# teensyMotors.net
KiCad netlist of a schematic drawn in EAGLE
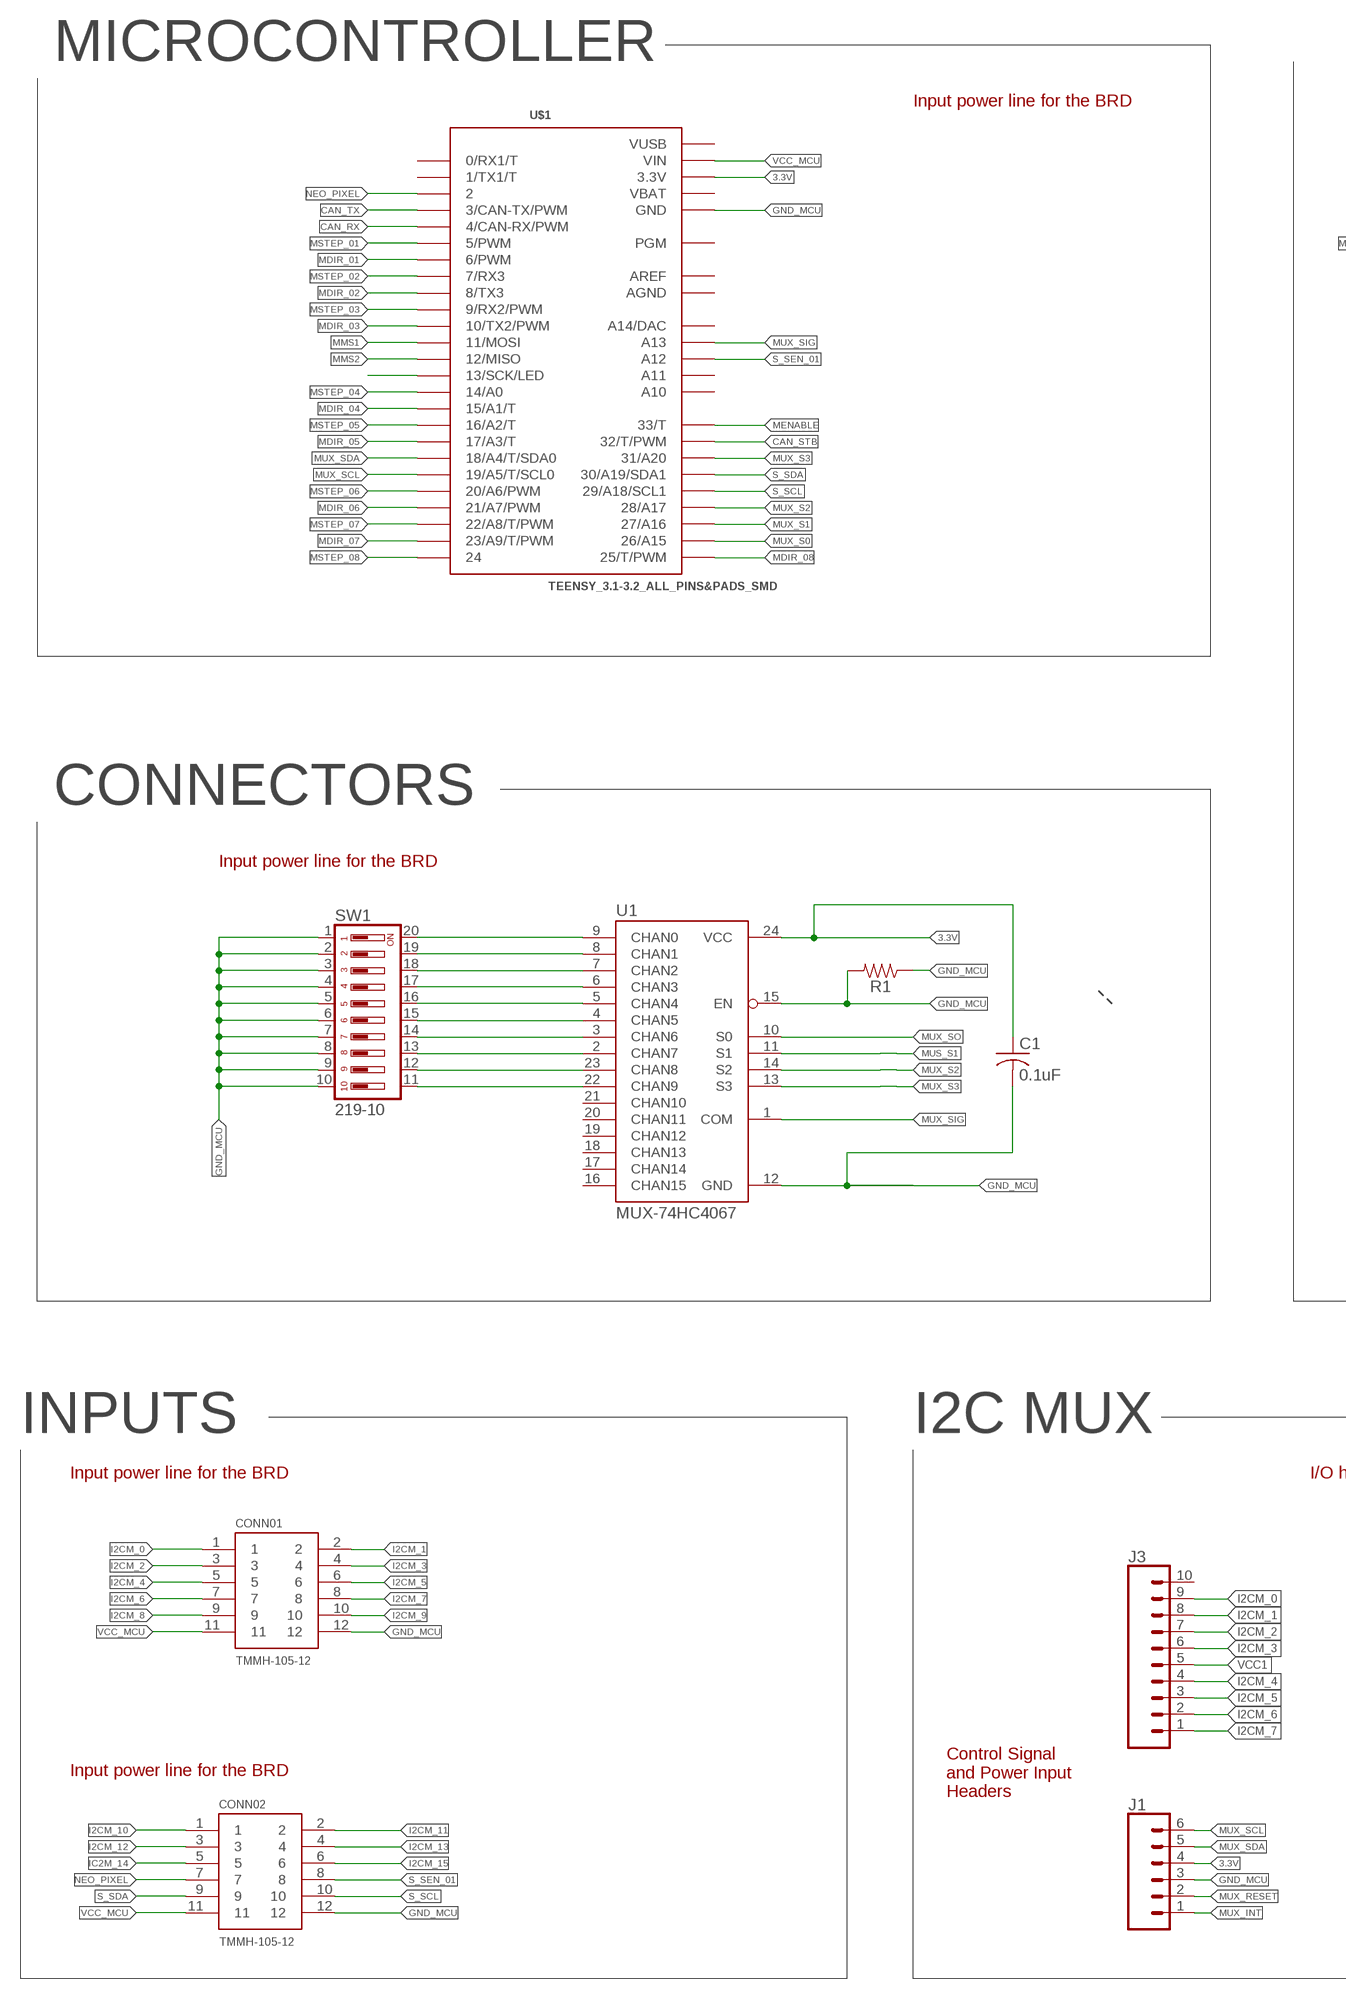
[diagram p0: schematic, sheet 1, part 1 of 2]
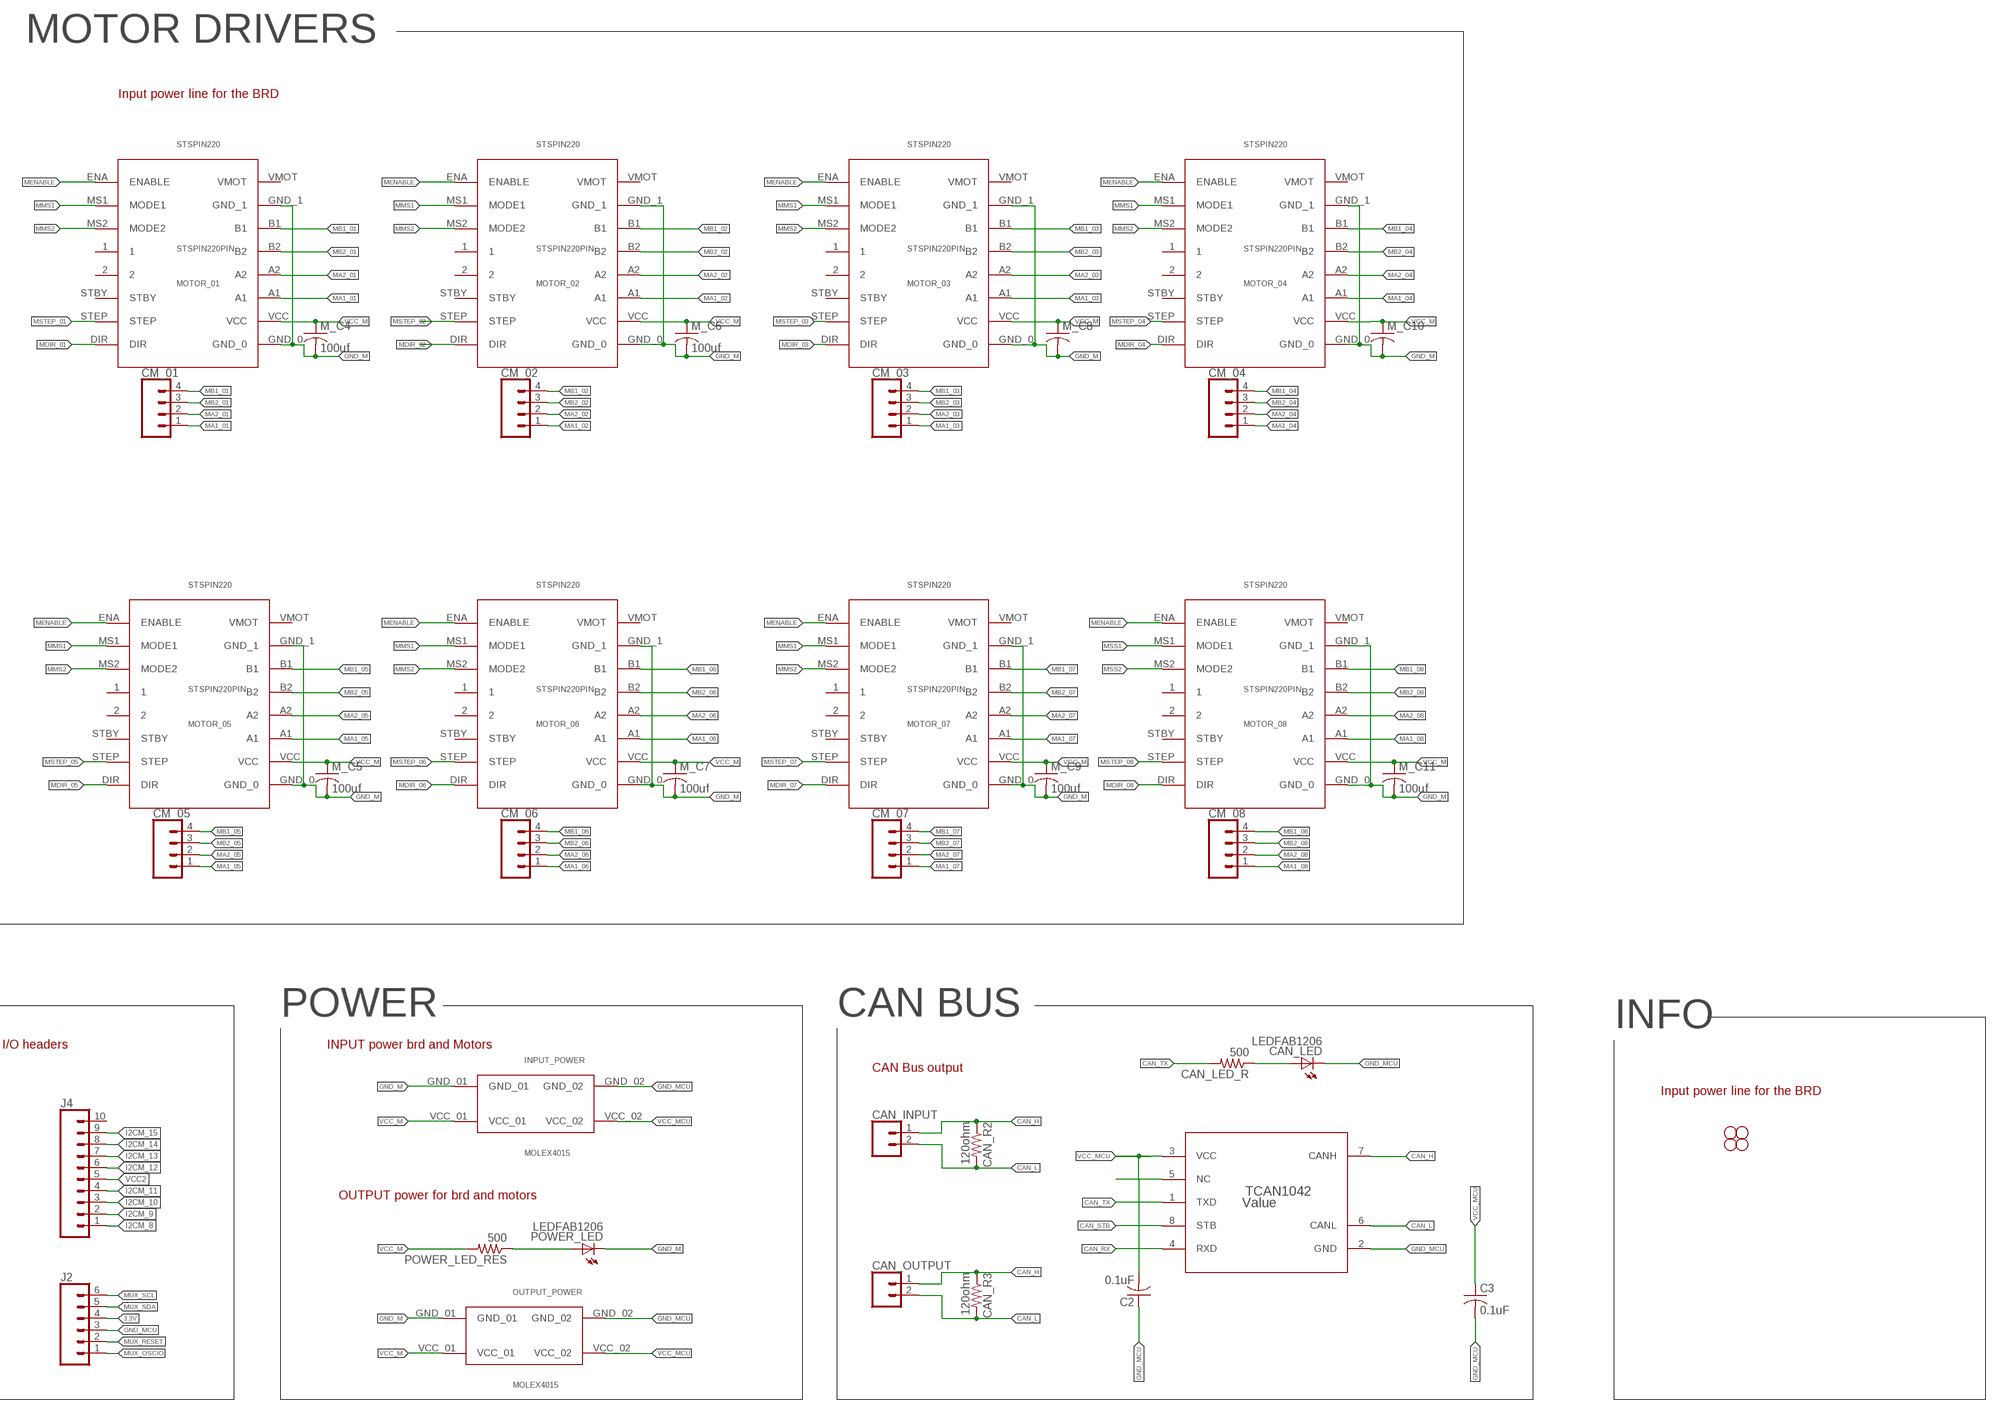
[diagram p1: schematic, sheet 1, part 2 of 2]

(export (version "E")
  (design (tool "Eeschema 10.0.6"))
  (components
    (comp (ref "C1")
      (value "0.1uF")
      (footprint "eagle-import:C1206")
      (libsource (lib "eagle-import") (part "C-USC1206"))
    )
    (comp (ref "C2")
      (value "0.1uF")
      (footprint "eagle-import:C1206")
      (libsource (lib "eagle-import") (part "C-USC1206"))
    )
    (comp (ref "C3")
      (value "0.1uF")
      (footprint "eagle-import:C1206")
      (libsource (lib "eagle-import") (part "C-USC1206"))
    )
    (comp (ref "CAN_INPUT")
      (value "CONN_02-JST-2MM-SMT")
      (footprint "eagle-import:JST-2-SMD")
      (libsource (lib "eagle-import") (part "CONN_02-JST-2MM-SMT"))
    )
    (comp (ref "CAN_LED")
      (value "LEDFAB1206")
      (footprint "eagle-import:LED1206FAB")
      (libsource (lib "eagle-import") (part "LEDFAB1206"))
    )
    (comp (ref "CAN_LED_R")
      (value "500")
      (footprint "eagle-import:R1206FAB")
      (libsource (lib "eagle-import") (part "RES-US1206FAB"))
    )
    (comp (ref "CAN_OUTPUT")
      (value "CONN_02-JST-2MM-SMT")
      (footprint "eagle-import:JST-2-SMD")
      (libsource (lib "eagle-import") (part "CONN_02-JST-2MM-SMT"))
    )
    (comp (ref "CAN_R2")
      (value "120ohm")
      (footprint "eagle-import:1206")
      (libsource (lib "eagle-import") (part "RESISTOR1206"))
    )
    (comp (ref "CAN_R3")
      (value "120ohm")
      (footprint "eagle-import:1206")
      (libsource (lib "eagle-import") (part "RESISTOR1206"))
    )
    (comp (ref "CM_01")
      (value "CONN_04SMD2")
      (footprint "eagle-import:1X04_1MM_RA")
      (libsource (lib "eagle-import") (part "CONN_04SMD2"))
    )
    (comp (ref "CM_02")
      (value "CONN_04SMD2")
      (footprint "eagle-import:1X04_1MM_RA")
      (libsource (lib "eagle-import") (part "CONN_04SMD2"))
    )
    (comp (ref "CM_03")
      (value "CONN_04SMD2")
      (footprint "eagle-import:1X04_1MM_RA")
      (libsource (lib "eagle-import") (part "CONN_04SMD2"))
    )
    (comp (ref "CM_04")
      (value "CONN_04SMD2")
      (footprint "eagle-import:1X04_1MM_RA")
      (libsource (lib "eagle-import") (part "CONN_04SMD2"))
    )
    (comp (ref "CM_05")
      (value "CONN_04SMD2")
      (footprint "eagle-import:1X04_1MM_RA")
      (libsource (lib "eagle-import") (part "CONN_04SMD2"))
    )
    (comp (ref "CM_06")
      (value "CONN_04SMD2")
      (footprint "eagle-import:1X04_1MM_RA")
      (libsource (lib "eagle-import") (part "CONN_04SMD2"))
    )
    (comp (ref "CM_07")
      (value "CONN_04SMD2")
      (footprint "eagle-import:1X04_1MM_RA")
      (libsource (lib "eagle-import") (part "CONN_04SMD2"))
    )
    (comp (ref "CM_08")
      (value "CONN_04SMD2")
      (footprint "eagle-import:1X04_1MM_RA")
      (libsource (lib "eagle-import") (part "CONN_04SMD2"))
    )
    (comp (ref "CONN01")
      (value "TMMH-105-12")
      (footprint "eagle-import:TMMH-105-12")
      (libsource (lib "eagle-import") (part "TMMH-105-12"))
    )
    (comp (ref "CONN02")
      (value "TMMH-105-12")
      (footprint "eagle-import:TMMH-105-12")
      (libsource (lib "eagle-import") (part "TMMH-105-12"))
    )
    (comp (ref "INPUT_POWER")
      (value "MOLEX4015")
      (footprint "eagle-import:MOLEX4015")
      (libsource (lib "eagle-import") (part "MOLEX4015"))
    )
    (comp (ref "J1")
      (value "CONN_06SMD_MALE")
      (footprint "eagle-import:1X06_SMD_MALE")
      (libsource (lib "eagle-import") (part "CONN_06SMD_MALE"))
    )
    (comp (ref "J2")
      (value "CONN_06SMD_MALE")
      (footprint "eagle-import:1X06_SMD_MALE")
      (libsource (lib "eagle-import") (part "CONN_06SMD_MALE"))
    )
    (comp (ref "J3")
      (value "CONN_10SMD_MALE")
      (footprint "eagle-import:1X10_SMD_MALE")
      (libsource (lib "eagle-import") (part "CONN_10SMD_MALE"))
    )
    (comp (ref "J4")
      (value "CONN_10SMD_MALE")
      (footprint "eagle-import:1X10_SMD_MALE")
      (libsource (lib "eagle-import") (part "CONN_10SMD_MALE"))
    )
    (comp (ref "MOTOR_01")
      (value "STSPIN220PIN")
      (footprint "eagle-import:STSPIN220")
      (libsource (lib "eagle-import") (part "STSPIN220PIN"))
    )
    (comp (ref "MOTOR_02")
      (value "STSPIN220PIN")
      (footprint "eagle-import:STSPIN220")
      (libsource (lib "eagle-import") (part "STSPIN220PIN"))
    )
    (comp (ref "MOTOR_03")
      (value "STSPIN220PIN")
      (footprint "eagle-import:STSPIN220")
      (libsource (lib "eagle-import") (part "STSPIN220PIN"))
    )
    (comp (ref "MOTOR_04")
      (value "STSPIN220PIN")
      (footprint "eagle-import:STSPIN220")
      (libsource (lib "eagle-import") (part "STSPIN220PIN"))
    )
    (comp (ref "MOTOR_05")
      (value "STSPIN220PIN")
      (footprint "eagle-import:STSPIN220")
      (libsource (lib "eagle-import") (part "STSPIN220PIN"))
    )
    (comp (ref "MOTOR_06")
      (value "STSPIN220PIN")
      (footprint "eagle-import:STSPIN220")
      (libsource (lib "eagle-import") (part "STSPIN220PIN"))
    )
    (comp (ref "MOTOR_07")
      (value "STSPIN220PIN")
      (footprint "eagle-import:STSPIN220")
      (libsource (lib "eagle-import") (part "STSPIN220PIN"))
    )
    (comp (ref "MOTOR_08")
      (value "STSPIN220PIN")
      (footprint "eagle-import:STSPIN220")
      (libsource (lib "eagle-import") (part "STSPIN220PIN"))
    )
    (comp (ref "M_C4")
      (value "100uf")
      (footprint "eagle-import:C1206")
      (libsource (lib "eagle-import") (part "C-USC1206"))
    )
    (comp (ref "M_C5")
      (value "100uf")
      (footprint "eagle-import:C1206")
      (libsource (lib "eagle-import") (part "C-USC1206"))
    )
    (comp (ref "M_C6")
      (value "100uf")
      (footprint "eagle-import:C1206")
      (libsource (lib "eagle-import") (part "C-USC1206"))
    )
    (comp (ref "M_C7")
      (value "100uf")
      (footprint "eagle-import:C1206")
      (libsource (lib "eagle-import") (part "C-USC1206"))
    )
    (comp (ref "M_C8")
      (value "C-USC1206")
      (footprint "eagle-import:C1206")
      (libsource (lib "eagle-import") (part "C-USC1206"))
    )
    (comp (ref "M_C9")
      (value "100uf")
      (footprint "eagle-import:C1206")
      (libsource (lib "eagle-import") (part "C-USC1206"))
    )
    (comp (ref "M_C10")
      (value "C-USC1206")
      (footprint "eagle-import:C1206")
      (libsource (lib "eagle-import") (part "C-USC1206"))
    )
    (comp (ref "M_C11")
      (value "100uf")
      (footprint "eagle-import:C1206")
      (libsource (lib "eagle-import") (part "C-USC1206"))
    )
    (comp (ref "OUTPUT_POWER")
      (value "MOLEX4015")
      (footprint "eagle-import:MOLEX4015")
      (libsource (lib "eagle-import") (part "MOLEX4015"))
    )
    (comp (ref "POWER_LED")
      (value "LEDFAB1206")
      (footprint "eagle-import:LED1206FAB")
      (libsource (lib "eagle-import") (part "LEDFAB1206"))
    )
    (comp (ref "POWER_LED_RES")
      (value "500")
      (footprint "eagle-import:R1206FAB")
      (libsource (lib "eagle-import") (part "RES-US1206FAB"))
    )
    (comp (ref "R1")
      (value "RESISTOR1206")
      (footprint "eagle-import:1206")
      (libsource (lib "eagle-import") (part "RESISTOR1206"))
    )
    (comp (ref "STANDOFF5")
      (value "STAND-OFF")
      (footprint "eagle-import:STAND-OFF")
      (libsource (lib "eagle-import") (part "STAND-OFF"))
    )
    (comp (ref "STANDOFF6")
      (value "STAND-OFF")
      (footprint "eagle-import:STAND-OFF")
      (libsource (lib "eagle-import") (part "STAND-OFF"))
    )
    (comp (ref "STANDOFF7")
      (value "STAND-OFF")
      (footprint "eagle-import:STAND-OFF")
      (libsource (lib "eagle-import") (part "STAND-OFF"))
    )
    (comp (ref "STANDOFF8")
      (value "STAND-OFF")
      (footprint "eagle-import:STAND-OFF")
      (libsource (lib "eagle-import") (part "STAND-OFF"))
    )
    (comp (ref "SW1")
      (value "219-10")
      (footprint "eagle-import:CTS-219-10")
      (fields (field (name "MF") "SLI (CML/IDI)") (field (name "MPN") "219-10PK"))
      (libsource (lib "eagle-import") (part "219-10"))
    )
    (comp (ref "TCAN1042")
      (value "Value")
      (footprint "eagle-import:D0008A_N")
      (fields (field (name "MANUFACTURER") "Texas Instruments") (field (name "PARTNUMBER") "TCAN1042DRQ1"))
      (libsource (lib "eagle-import") (part "TCAN1042DRQ1"))
    )
    (comp (ref "U$1")
      (value "TEENSY_3.1-3.2_ALL_PINS&PADS_SMD")
      (footprint "eagle-import:TEENSY_3.0-3.2_ALL_PINS_&_PADS_SMD")
      (libsource (lib "eagle-import") (part "TEENSY_3.1-3.2_ALL_PINS&PADS_SMD"))
    )
    (comp (ref "U1")
      (value "MUX-74HC4067")
      (footprint "eagle-import:SSOP24")
      (libsource (lib "eagle-import") (part "MUX-74HC4067SMD"))
    )
  )
  (nets
    (net (code "1") (name "/AGND") (class "Default")
      (node (ref "U$1") (pin "AGND") (pinfunction "AGND_AGND") (pintype "power_in"))
    )
    (net (code "2") (name "/AREF") (class "Default")
      (node (ref "U$1") (pin "AREF") (pinfunction "AREF_AREF") (pintype "power_in"))
    )
    (net (code "3") (name "/VBAT") (class "Default")
      (node (ref "U$1") (pin "VBAT") (pinfunction "VBAT_VBAT") (pintype "power_in"))
    )
    (net (code "4") (name "/VUSB") (class "Default")
      (node (ref "U$1") (pin "VUSB") (pinfunction "VUSB_VUSB") (pintype "power_in"))
    )
    (net (code "5") (name "3.3V") (class "Default")
      (node (ref "C1") (pin "1") (pinfunction "1_1") (pintype "passive"))
      (node (ref "J1") (pin "4") (pinfunction "4_4") (pintype "passive"))
      (node (ref "J2") (pin "4") (pinfunction "4_4") (pintype "passive"))
      (node (ref "U$1") (pin "3.3V") (pinfunction "3.3V_3.3V") (pintype "power_in"))
      (node (ref "U$1") (pin "3.3V1") (pinfunction "3.3V_3.3V1") (pintype "power_in"))
      (node (ref "U$1") (pin "3.3V2") (pinfunction "3.3V_3.3V2") (pintype "power_in"))
      (node (ref "U1") (pin "24") (pinfunction "VCC_24") (pintype "bidirectional"))
    )
    (net (code "6") (name "CAN_H") (class "Default")
      (node (ref "CAN_INPUT") (pin "1") (pinfunction "2_1") (pintype "passive"))
      (node (ref "CAN_OUTPUT") (pin "1") (pinfunction "2_1") (pintype "passive"))
      (node (ref "CAN_R2") (pin "1") (pinfunction "1_1") (pintype "passive"))
      (node (ref "CAN_R3") (pin "1") (pinfunction "1_1") (pintype "passive"))
      (node (ref "TCAN1042") (pin "7") (pinfunction "CANH_7") (pintype "bidirectional"))
    )
    (net (code "7") (name "CAN_L") (class "Default")
      (node (ref "CAN_INPUT") (pin "2") (pinfunction "1_2") (pintype "passive"))
      (node (ref "CAN_OUTPUT") (pin "2") (pinfunction "1_2") (pintype "passive"))
      (node (ref "CAN_R2") (pin "2") (pinfunction "2_2") (pintype "passive"))
      (node (ref "CAN_R3") (pin "2") (pinfunction "2_2") (pintype "passive"))
      (node (ref "TCAN1042") (pin "6") (pinfunction "CANL_6") (pintype "bidirectional"))
    )
    (net (code "8") (name "CAN_RX") (class "Default")
      (node (ref "TCAN1042") (pin "4") (pinfunction "RXD_4") (pintype "output"))
      (node (ref "U$1") (pin "4") (pinfunction "4/CAN-RX/PWM_4") (pintype "bidirectional"))
    )
    (net (code "9") (name "CAN_STB") (class "Default")
      (node (ref "TCAN1042") (pin "8") (pinfunction "STB_8") (pintype "input"))
      (node (ref "U$1") (pin "32") (pinfunction "32/T/PWM_32") (pintype "bidirectional"))
    )
    (net (code "10") (name "CAN_TX") (class "Default")
      (node (ref "CAN_LED_R") (pin "2") (pinfunction "2_2") (pintype "passive"))
      (node (ref "TCAN1042") (pin "1") (pinfunction "TXD_1") (pintype "input"))
      (node (ref "U$1") (pin "3") (pinfunction "3/CAN-TX/PWM_3") (pintype "bidirectional"))
    )
    (net (code "11") (name "GND_M") (class "Default")
      (node (ref "INPUT_POWER") (pin "GND_01") (pinfunction "GND_01_GND_01") (pintype "bidirectional"))
      (node (ref "MOTOR_01") (pin "GND_0") (pinfunction "GND_0_GND_0") (pintype "bidirectional"))
      (node (ref "MOTOR_01") (pin "GND_1") (pinfunction "GND_1_GND_1") (pintype "bidirectional"))
      (node (ref "MOTOR_02") (pin "GND_0") (pinfunction "GND_0_GND_0") (pintype "bidirectional"))
      (node (ref "MOTOR_02") (pin "GND_1") (pinfunction "GND_1_GND_1") (pintype "bidirectional"))
      (node (ref "MOTOR_03") (pin "GND_0") (pinfunction "GND_0_GND_0") (pintype "bidirectional"))
      (node (ref "MOTOR_03") (pin "GND_1") (pinfunction "GND_1_GND_1") (pintype "bidirectional"))
      (node (ref "MOTOR_04") (pin "GND_0") (pinfunction "GND_0_GND_0") (pintype "bidirectional"))
      (node (ref "MOTOR_04") (pin "GND_1") (pinfunction "GND_1_GND_1") (pintype "bidirectional"))
      (node (ref "MOTOR_05") (pin "GND_0") (pinfunction "GND_0_GND_0") (pintype "bidirectional"))
      (node (ref "MOTOR_05") (pin "GND_1") (pinfunction "GND_1_GND_1") (pintype "bidirectional"))
      (node (ref "MOTOR_06") (pin "GND_0") (pinfunction "GND_0_GND_0") (pintype "bidirectional"))
      (node (ref "MOTOR_06") (pin "GND_1") (pinfunction "GND_1_GND_1") (pintype "bidirectional"))
      (node (ref "MOTOR_07") (pin "GND_0") (pinfunction "GND_0_GND_0") (pintype "bidirectional"))
      (node (ref "MOTOR_07") (pin "GND_1") (pinfunction "GND_1_GND_1") (pintype "bidirectional"))
      (node (ref "MOTOR_08") (pin "GND_0") (pinfunction "GND_0_GND_0") (pintype "bidirectional"))
      (node (ref "MOTOR_08") (pin "GND_1") (pinfunction "GND_1_GND_1") (pintype "bidirectional"))
      (node (ref "M_C10") (pin "2") (pinfunction "2_2") (pintype "passive"))
      (node (ref "M_C11") (pin "2") (pinfunction "2_2") (pintype "passive"))
      (node (ref "M_C4") (pin "2") (pinfunction "2_2") (pintype "passive"))
      (node (ref "M_C5") (pin "2") (pinfunction "2_2") (pintype "passive"))
      (node (ref "M_C6") (pin "2") (pinfunction "2_2") (pintype "passive"))
      (node (ref "M_C7") (pin "2") (pinfunction "2_2") (pintype "passive"))
      (node (ref "M_C8") (pin "2") (pinfunction "2_2") (pintype "passive"))
      (node (ref "M_C9") (pin "2") (pinfunction "2_2") (pintype "passive"))
      (node (ref "OUTPUT_POWER") (pin "GND_01") (pinfunction "GND_01_GND_01") (pintype "bidirectional"))
      (node (ref "POWER_LED") (pin "2") (pinfunction "C_2") (pintype "passive"))
    )
    (net (code "12") (name "GND_MCU") (class "Default")
      (node (ref "C1") (pin "2") (pinfunction "2_2") (pintype "passive"))
      (node (ref "C2") (pin "1") (pinfunction "1_1") (pintype "passive"))
      (node (ref "C3") (pin "2") (pinfunction "2_2") (pintype "passive"))
      (node (ref "CAN_LED") (pin "2") (pinfunction "C_2") (pintype "passive"))
      (node (ref "CONN01") (pin "12") (pinfunction "12_12") (pintype "bidirectional"))
      (node (ref "CONN02") (pin "12") (pinfunction "12_12") (pintype "bidirectional"))
      (node (ref "INPUT_POWER") (pin "GND_02") (pinfunction "GND_02_GND_02") (pintype "bidirectional"))
      (node (ref "J1") (pin "3") (pinfunction "3_3") (pintype "passive"))
      (node (ref "J2") (pin "3") (pinfunction "3_3") (pintype "passive"))
      (node (ref "OUTPUT_POWER") (pin "GND_02") (pinfunction "GND_02_GND_02") (pintype "bidirectional"))
      (node (ref "R1") (pin "1") (pinfunction "1_1") (pintype "passive"))
      (node (ref "R1") (pin "2") (pinfunction "2_2") (pintype "passive"))
      (node (ref "SW1") (pin "1") (pinfunction "1_1") (pintype "passive"))
      (node (ref "SW1") (pin "10") (pinfunction "10_10") (pintype "passive"))
      (node (ref "SW1") (pin "2") (pinfunction "2_2") (pintype "passive"))
      (node (ref "SW1") (pin "3") (pinfunction "3_3") (pintype "passive"))
      (node (ref "SW1") (pin "4") (pinfunction "4_4") (pintype "passive"))
      (node (ref "SW1") (pin "5") (pinfunction "5_5") (pintype "passive"))
      (node (ref "SW1") (pin "6") (pinfunction "6_6") (pintype "passive"))
      (node (ref "SW1") (pin "7") (pinfunction "7_7") (pintype "passive"))
      (node (ref "SW1") (pin "8") (pinfunction "8_8") (pintype "passive"))
      (node (ref "SW1") (pin "9") (pinfunction "9_9") (pintype "passive"))
      (node (ref "TCAN1042") (pin "2") (pinfunction "GND_2") (pintype "power_in"))
      (node (ref "U$1") (pin "GND") (pinfunction "GND_GND") (pintype "power_in"))
      (node (ref "U$1") (pin "GND1") (pinfunction "GND_GND1") (pintype "power_in"))
      (node (ref "U$1") (pin "GND2") (pinfunction "GND_GND2") (pintype "power_in"))
      (node (ref "U1") (pin "12") (pinfunction "GND_12") (pintype "bidirectional"))
      (node (ref "U1") (pin "15") (pinfunction "EN_15") (pintype "input"))
    )
    (net (code "13") (name "I2CM_0") (class "Default")
      (node (ref "CONN01") (pin "1") (pinfunction "1_1") (pintype "bidirectional"))
      (node (ref "J3") (pin "9") (pinfunction "9_9") (pintype "passive"))
    )
    (net (code "14") (name "I2CM_1") (class "Default")
      (node (ref "CONN01") (pin "2") (pinfunction "2_2") (pintype "bidirectional"))
      (node (ref "J3") (pin "8") (pinfunction "8_8") (pintype "passive"))
    )
    (net (code "15") (name "I2CM_2") (class "Default")
      (node (ref "CONN01") (pin "3") (pinfunction "3_3") (pintype "bidirectional"))
      (node (ref "J3") (pin "7") (pinfunction "7_7") (pintype "passive"))
    )
    (net (code "16") (name "I2CM_3") (class "Default")
      (node (ref "CONN01") (pin "4") (pinfunction "4_4") (pintype "bidirectional"))
      (node (ref "J3") (pin "6") (pinfunction "6_6") (pintype "passive"))
    )
    (net (code "17") (name "I2CM_4") (class "Default")
      (node (ref "CONN01") (pin "5") (pinfunction "5_5") (pintype "bidirectional"))
      (node (ref "J3") (pin "4") (pinfunction "4_4") (pintype "passive"))
    )
    (net (code "18") (name "I2CM_5") (class "Default")
      (node (ref "CONN01") (pin "6") (pinfunction "6_6") (pintype "bidirectional"))
      (node (ref "J3") (pin "3") (pinfunction "3_3") (pintype "passive"))
    )
    (net (code "19") (name "I2CM_6") (class "Default")
      (node (ref "CONN01") (pin "7") (pinfunction "7_7") (pintype "bidirectional"))
      (node (ref "J3") (pin "2") (pinfunction "2_2") (pintype "passive"))
    )
    (net (code "20") (name "I2CM_7") (class "Default")
      (node (ref "CONN01") (pin "8") (pinfunction "8_8") (pintype "bidirectional"))
      (node (ref "J3") (pin "1") (pinfunction "1_1") (pintype "passive"))
    )
    (net (code "21") (name "I2CM_8") (class "Default")
      (node (ref "CONN01") (pin "9") (pinfunction "9_9") (pintype "bidirectional"))
      (node (ref "J4") (pin "1") (pinfunction "1_1") (pintype "passive"))
    )
    (net (code "22") (name "I2CM_9") (class "Default")
      (node (ref "CONN01") (pin "10") (pinfunction "10_10") (pintype "bidirectional"))
      (node (ref "J4") (pin "2") (pinfunction "2_2") (pintype "passive"))
    )
    (net (code "23") (name "I2CM_10") (class "Default")
      (node (ref "CONN02") (pin "1") (pinfunction "1_1") (pintype "bidirectional"))
      (node (ref "J4") (pin "3") (pinfunction "3_3") (pintype "passive"))
    )
    (net (code "24") (name "I2CM_11") (class "Default")
      (node (ref "CONN02") (pin "2") (pinfunction "2_2") (pintype "bidirectional"))
      (node (ref "J4") (pin "4") (pinfunction "4_4") (pintype "passive"))
    )
    (net (code "25") (name "I2CM_12") (class "Default")
      (node (ref "CONN02") (pin "3") (pinfunction "3_3") (pintype "bidirectional"))
      (node (ref "J4") (pin "6") (pinfunction "6_6") (pintype "passive"))
    )
    (net (code "26") (name "I2CM_13") (class "Default")
      (node (ref "CONN02") (pin "4") (pinfunction "4_4") (pintype "bidirectional"))
      (node (ref "J4") (pin "7") (pinfunction "7_7") (pintype "passive"))
    )
    (net (code "27") (name "I2CM_14") (class "Default")
      (node (ref "J4") (pin "8") (pinfunction "8_8") (pintype "passive"))
    )
    (net (code "28") (name "I2CM_15") (class "Default")
      (node (ref "CONN02") (pin "6") (pinfunction "6_6") (pintype "bidirectional"))
      (node (ref "J4") (pin "9") (pinfunction "9_9") (pintype "passive"))
    )
    (net (code "29") (name "IC2M_14") (class "Default")
      (node (ref "CONN02") (pin "5") (pinfunction "5_5") (pintype "bidirectional"))
    )
    (net (code "30") (name "MA1_01") (class "Default")
      (node (ref "CM_01") (pin "1") (pinfunction "1_1") (pintype "passive"))
      (node (ref "MOTOR_01") (pin "A1") (pinfunction "A1_A1") (pintype "bidirectional"))
    )
    (net (code "31") (name "MA1_02") (class "Default")
      (node (ref "CM_02") (pin "1") (pinfunction "1_1") (pintype "passive"))
      (node (ref "MOTOR_02") (pin "A1") (pinfunction "A1_A1") (pintype "bidirectional"))
    )
    (net (code "32") (name "MA1_03") (class "Default")
      (node (ref "CM_03") (pin "1") (pinfunction "1_1") (pintype "passive"))
      (node (ref "MOTOR_03") (pin "A1") (pinfunction "A1_A1") (pintype "bidirectional"))
    )
    (net (code "33") (name "MA1_04") (class "Default")
      (node (ref "CM_04") (pin "1") (pinfunction "1_1") (pintype "passive"))
      (node (ref "MOTOR_04") (pin "A1") (pinfunction "A1_A1") (pintype "bidirectional"))
    )
    (net (code "34") (name "MA1_05") (class "Default")
      (node (ref "CM_05") (pin "1") (pinfunction "1_1") (pintype "passive"))
      (node (ref "MOTOR_05") (pin "A1") (pinfunction "A1_A1") (pintype "bidirectional"))
    )
    (net (code "35") (name "MA1_06") (class "Default")
      (node (ref "CM_06") (pin "1") (pinfunction "1_1") (pintype "passive"))
      (node (ref "MOTOR_06") (pin "A1") (pinfunction "A1_A1") (pintype "bidirectional"))
    )
    (net (code "36") (name "MA1_07") (class "Default")
      (node (ref "CM_07") (pin "1") (pinfunction "1_1") (pintype "passive"))
      (node (ref "MOTOR_07") (pin "A1") (pinfunction "A1_A1") (pintype "bidirectional"))
    )
    (net (code "37") (name "MA1_08") (class "Default")
      (node (ref "CM_08") (pin "1") (pinfunction "1_1") (pintype "passive"))
      (node (ref "MOTOR_08") (pin "A1") (pinfunction "A1_A1") (pintype "bidirectional"))
    )
    (net (code "38") (name "MA2_01") (class "Default")
      (node (ref "CM_01") (pin "2") (pinfunction "2_2") (pintype "passive"))
      (node (ref "MOTOR_01") (pin "A2") (pinfunction "A2_A2") (pintype "bidirectional"))
    )
    (net (code "39") (name "MA2_02") (class "Default")
      (node (ref "CM_02") (pin "2") (pinfunction "2_2") (pintype "passive"))
      (node (ref "MOTOR_02") (pin "A2") (pinfunction "A2_A2") (pintype "bidirectional"))
    )
    (net (code "40") (name "MA2_03") (class "Default")
      (node (ref "CM_03") (pin "2") (pinfunction "2_2") (pintype "passive"))
      (node (ref "MOTOR_03") (pin "A2") (pinfunction "A2_A2") (pintype "bidirectional"))
    )
    (net (code "41") (name "MA2_04") (class "Default")
      (node (ref "CM_04") (pin "2") (pinfunction "2_2") (pintype "passive"))
      (node (ref "MOTOR_04") (pin "A2") (pinfunction "A2_A2") (pintype "bidirectional"))
    )
    (net (code "42") (name "MA2_05") (class "Default")
      (node (ref "CM_05") (pin "2") (pinfunction "2_2") (pintype "passive"))
      (node (ref "MOTOR_05") (pin "A2") (pinfunction "A2_A2") (pintype "bidirectional"))
    )
    (net (code "43") (name "MA2_06") (class "Default")
      (node (ref "CM_06") (pin "2") (pinfunction "2_2") (pintype "passive"))
      (node (ref "MOTOR_06") (pin "A2") (pinfunction "A2_A2") (pintype "bidirectional"))
    )
    (net (code "44") (name "MA2_07") (class "Default")
      (node (ref "CM_07") (pin "2") (pinfunction "2_2") (pintype "passive"))
      (node (ref "MOTOR_07") (pin "A2") (pinfunction "A2_A2") (pintype "bidirectional"))
    )
    (net (code "45") (name "MA2_08") (class "Default")
      (node (ref "CM_08") (pin "2") (pinfunction "2_2") (pintype "passive"))
      (node (ref "MOTOR_08") (pin "A2") (pinfunction "A2_A2") (pintype "bidirectional"))
    )
    (net (code "46") (name "MB1_01") (class "Default")
      (node (ref "CM_01") (pin "4") (pinfunction "4_4") (pintype "passive"))
      (node (ref "MOTOR_01") (pin "B1") (pinfunction "B1_B1") (pintype "bidirectional"))
    )
    (net (code "47") (name "MB1_02") (class "Default")
      (node (ref "CM_02") (pin "4") (pinfunction "4_4") (pintype "passive"))
      (node (ref "MOTOR_02") (pin "B1") (pinfunction "B1_B1") (pintype "bidirectional"))
    )
    (net (code "48") (name "MB1_03") (class "Default")
      (node (ref "CM_03") (pin "4") (pinfunction "4_4") (pintype "passive"))
      (node (ref "MOTOR_03") (pin "B1") (pinfunction "B1_B1") (pintype "bidirectional"))
    )
    (net (code "49") (name "MB1_04") (class "Default")
      (node (ref "CM_04") (pin "4") (pinfunction "4_4") (pintype "passive"))
      (node (ref "MOTOR_04") (pin "B1") (pinfunction "B1_B1") (pintype "bidirectional"))
    )
    (net (code "50") (name "MB1_05") (class "Default")
      (node (ref "CM_05") (pin "4") (pinfunction "4_4") (pintype "passive"))
      (node (ref "MOTOR_05") (pin "B1") (pinfunction "B1_B1") (pintype "bidirectional"))
    )
    (net (code "51") (name "MB1_06") (class "Default")
      (node (ref "CM_06") (pin "4") (pinfunction "4_4") (pintype "passive"))
      (node (ref "MOTOR_06") (pin "B1") (pinfunction "B1_B1") (pintype "bidirectional"))
    )
    (net (code "52") (name "MB1_07") (class "Default")
      (node (ref "CM_07") (pin "4") (pinfunction "4_4") (pintype "passive"))
      (node (ref "MOTOR_07") (pin "B1") (pinfunction "B1_B1") (pintype "bidirectional"))
    )
    (net (code "53") (name "MB1_08") (class "Default")
      (node (ref "CM_08") (pin "4") (pinfunction "4_4") (pintype "passive"))
      (node (ref "MOTOR_08") (pin "B1") (pinfunction "B1_B1") (pintype "bidirectional"))
    )
    (net (code "54") (name "MB2_01") (class "Default")
      (node (ref "CM_01") (pin "3") (pinfunction "3_3") (pintype "passive"))
      (node (ref "MOTOR_01") (pin "B2") (pinfunction "B2_B2") (pintype "bidirectional"))
    )
    (net (code "55") (name "MB2_02") (class "Default")
      (node (ref "CM_02") (pin "3") (pinfunction "3_3") (pintype "passive"))
      (node (ref "MOTOR_02") (pin "B2") (pinfunction "B2_B2") (pintype "bidirectional"))
    )
    (net (code "56") (name "MB2_03") (class "Default")
      (node (ref "CM_03") (pin "3") (pinfunction "3_3") (pintype "passive"))
      (node (ref "MOTOR_03") (pin "B2") (pinfunction "B2_B2") (pintype "bidirectional"))
    )
    (net (code "57") (name "MB2_04") (class "Default")
      (node (ref "CM_04") (pin "3") (pinfunction "3_3") (pintype "passive"))
      (node (ref "MOTOR_04") (pin "B2") (pinfunction "B2_B2") (pintype "bidirectional"))
    )
    (net (code "58") (name "MB2_05") (class "Default")
      (node (ref "CM_05") (pin "3") (pinfunction "3_3") (pintype "passive"))
      (node (ref "MOTOR_05") (pin "B2") (pinfunction "B2_B2") (pintype "bidirectional"))
    )
    (net (code "59") (name "MB2_06") (class "Default")
      (node (ref "CM_06") (pin "3") (pinfunction "3_3") (pintype "passive"))
      (node (ref "MOTOR_06") (pin "B2") (pinfunction "B2_B2") (pintype "bidirectional"))
    )
    (net (code "60") (name "MB2_07") (class "Default")
      (node (ref "CM_07") (pin "3") (pinfunction "3_3") (pintype "passive"))
      (node (ref "MOTOR_07") (pin "B2") (pinfunction "B2_B2") (pintype "bidirectional"))
    )
    (net (code "61") (name "MB2_08") (class "Default")
      (node (ref "CM_08") (pin "3") (pinfunction "3_3") (pintype "passive"))
      (node (ref "MOTOR_08") (pin "B2") (pinfunction "B2_B2") (pintype "bidirectional"))
    )
    (net (code "62") (name "MDIR_01") (class "Default")
      (node (ref "MOTOR_01") (pin "DIR") (pinfunction "DIR_DIR") (pintype "bidirectional"))
      (node (ref "U$1") (pin "6") (pinfunction "6/PWM_6") (pintype "bidirectional"))
    )
    (net (code "63") (name "MDIR_02") (class "Default")
      (node (ref "MOTOR_02") (pin "DIR") (pinfunction "DIR_DIR") (pintype "bidirectional"))
      (node (ref "U$1") (pin "8") (pinfunction "8/TX3_8") (pintype "bidirectional"))
    )
    (net (code "64") (name "MDIR_03") (class "Default")
      (node (ref "MOTOR_03") (pin "DIR") (pinfunction "DIR_DIR") (pintype "bidirectional"))
      (node (ref "U$1") (pin "10") (pinfunction "10/TX2/PWM_10") (pintype "bidirectional"))
    )
    (net (code "65") (name "MDIR_04") (class "Default")
      (node (ref "MOTOR_04") (pin "DIR") (pinfunction "DIR_DIR") (pintype "bidirectional"))
      (node (ref "U$1") (pin "15/A1") (pinfunction "15/A1/T_15/A1") (pintype "bidirectional"))
    )
    (net (code "66") (name "MDIR_05") (class "Default")
      (node (ref "MOTOR_05") (pin "DIR") (pinfunction "DIR_DIR") (pintype "bidirectional"))
      (node (ref "U$1") (pin "17/A3") (pinfunction "17/A3/T_17/A3") (pintype "bidirectional"))
    )
    (net (code "67") (name "MDIR_06") (class "Default")
      (node (ref "MOTOR_06") (pin "DIR") (pinfunction "DIR_DIR") (pintype "bidirectional"))
      (node (ref "U$1") (pin "21/A7") (pinfunction "21/A7/PWM_21/A7") (pintype "bidirectional"))
    )
    (net (code "68") (name "MDIR_07") (class "Default")
      (node (ref "MOTOR_07") (pin "DIR") (pinfunction "DIR_DIR") (pintype "bidirectional"))
      (node (ref "U$1") (pin "23/A9") (pinfunction "23/A9/T/PWM_23/A9") (pintype "bidirectional"))
    )
    (net (code "69") (name "MDIR_08") (class "Default")
      (node (ref "MOTOR_08") (pin "DIR") (pinfunction "DIR_DIR") (pintype "bidirectional"))
      (node (ref "U$1") (pin "25") (pinfunction "25/T/PWM_25") (pintype "bidirectional"))
    )
    (net (code "70") (name "MENABLE") (class "Default")
      (node (ref "MOTOR_01") (pin "ENA") (pinfunction "ENABLE_ENA") (pintype "bidirectional"))
      (node (ref "MOTOR_02") (pin "ENA") (pinfunction "ENABLE_ENA") (pintype "bidirectional"))
      (node (ref "MOTOR_03") (pin "ENA") (pinfunction "ENABLE_ENA") (pintype "bidirectional"))
      (node (ref "MOTOR_04") (pin "ENA") (pinfunction "ENABLE_ENA") (pintype "bidirectional"))
      (node (ref "MOTOR_05") (pin "ENA") (pinfunction "ENABLE_ENA") (pintype "bidirectional"))
      (node (ref "MOTOR_06") (pin "ENA") (pinfunction "ENABLE_ENA") (pintype "bidirectional"))
      (node (ref "MOTOR_07") (pin "ENA") (pinfunction "ENABLE_ENA") (pintype "bidirectional"))
      (node (ref "MOTOR_08") (pin "ENA") (pinfunction "ENABLE_ENA") (pintype "bidirectional"))
      (node (ref "U$1") (pin "33") (pinfunction "33/T_33") (pintype "bidirectional"))
    )
    (net (code "71") (name "MMS1") (class "Default")
      (node (ref "MOTOR_01") (pin "MS1") (pinfunction "MODE1_MS1") (pintype "bidirectional"))
      (node (ref "MOTOR_02") (pin "MS1") (pinfunction "MODE1_MS1") (pintype "bidirectional"))
      (node (ref "MOTOR_03") (pin "MS1") (pinfunction "MODE1_MS1") (pintype "bidirectional"))
      (node (ref "MOTOR_04") (pin "MS1") (pinfunction "MODE1_MS1") (pintype "bidirectional"))
      (node (ref "MOTOR_05") (pin "MS1") (pinfunction "MODE1_MS1") (pintype "bidirectional"))
      (node (ref "MOTOR_06") (pin "MS1") (pinfunction "MODE1_MS1") (pintype "bidirectional"))
      (node (ref "MOTOR_07") (pin "MS1") (pinfunction "MODE1_MS1") (pintype "bidirectional"))
      (node (ref "U$1") (pin "11") (pinfunction "11/MOSI_11") (pintype "bidirectional"))
    )
    (net (code "72") (name "MMS2") (class "Default")
      (node (ref "MOTOR_01") (pin "MS2") (pinfunction "MODE2_MS2") (pintype "bidirectional"))
      (node (ref "MOTOR_02") (pin "MS2") (pinfunction "MODE2_MS2") (pintype "bidirectional"))
      (node (ref "MOTOR_03") (pin "MS2") (pinfunction "MODE2_MS2") (pintype "bidirectional"))
      (node (ref "MOTOR_04") (pin "MS2") (pinfunction "MODE2_MS2") (pintype "bidirectional"))
      (node (ref "MOTOR_05") (pin "MS2") (pinfunction "MODE2_MS2") (pintype "bidirectional"))
      (node (ref "MOTOR_06") (pin "MS2") (pinfunction "MODE2_MS2") (pintype "bidirectional"))
      (node (ref "MOTOR_07") (pin "MS2") (pinfunction "MODE2_MS2") (pintype "bidirectional"))
      (node (ref "U$1") (pin "12") (pinfunction "12/MISO_12") (pintype "bidirectional"))
    )
    (net (code "73") (name "MSS1") (class "Default")
      (node (ref "MOTOR_08") (pin "MS1") (pinfunction "MODE1_MS1") (pintype "bidirectional"))
    )
    (net (code "74") (name "MSS2") (class "Default")
      (node (ref "MOTOR_08") (pin "MS2") (pinfunction "MODE2_MS2") (pintype "bidirectional"))
    )
    (net (code "75") (name "MSTEP_01") (class "Default")
      (node (ref "MOTOR_01") (pin "STEP") (pinfunction "STEP_STEP") (pintype "bidirectional"))
      (node (ref "U$1") (pin "5") (pinfunction "5/PWM_5") (pintype "bidirectional"))
    )
    (net (code "76") (name "MSTEP_02") (class "Default")
      (node (ref "MOTOR_02") (pin "STEP") (pinfunction "STEP_STEP") (pintype "bidirectional"))
      (node (ref "U$1") (pin "7") (pinfunction "7/RX3_7") (pintype "bidirectional"))
    )
    (net (code "77") (name "MSTEP_03") (class "Default")
      (node (ref "MOTOR_03") (pin "STEP") (pinfunction "STEP_STEP") (pintype "bidirectional"))
      (node (ref "U$1") (pin "9") (pinfunction "9/RX2/PWM_9") (pintype "bidirectional"))
    )
    (net (code "78") (name "MSTEP_04") (class "Default")
      (node (ref "MOTOR_04") (pin "STEP") (pinfunction "STEP_STEP") (pintype "bidirectional"))
      (node (ref "U$1") (pin "14/A0") (pinfunction "14/A0_14/A0") (pintype "bidirectional"))
    )
    (net (code "79") (name "MSTEP_05") (class "Default")
      (node (ref "MOTOR_05") (pin "STEP") (pinfunction "STEP_STEP") (pintype "bidirectional"))
      (node (ref "U$1") (pin "16/A2") (pinfunction "16/A2/T_16/A2") (pintype "bidirectional"))
    )
    (net (code "80") (name "MSTEP_06") (class "Default")
      (node (ref "MOTOR_06") (pin "STEP") (pinfunction "STEP_STEP") (pintype "bidirectional"))
      (node (ref "U$1") (pin "20/A6") (pinfunction "20/A6/PWM_20/A6") (pintype "bidirectional"))
    )
    (net (code "81") (name "MSTEP_07") (class "Default")
      (node (ref "MOTOR_07") (pin "STEP") (pinfunction "STEP_STEP") (pintype "bidirectional"))
      (node (ref "U$1") (pin "22/A8") (pinfunction "22/A8/T/PWM_22/A8") (pintype "bidirectional"))
    )
    (net (code "82") (name "MSTEP_08") (class "Default")
      (node (ref "MOTOR_08") (pin "STEP") (pinfunction "STEP_STEP") (pintype "bidirectional"))
      (node (ref "U$1") (pin "24") (pinfunction "24_24") (pintype "bidirectional"))
    )
    (net (code "83") (name "MUS_S1") (class "Default")
      (node (ref "U1") (pin "11") (pinfunction "S1_11") (pintype "input"))
    )
    (net (code "84") (name "MUX_INT") (class "Default")
      (node (ref "J1") (pin "1") (pinfunction "1_1") (pintype "passive"))
    )
    (net (code "85") (name "MUX_OSCIO") (class "Default")
      (node (ref "J2") (pin "1") (pinfunction "1_1") (pintype "passive"))
    )
    (net (code "86") (name "MUX_RESET") (class "Default")
      (node (ref "J1") (pin "2") (pinfunction "2_2") (pintype "passive"))
      (node (ref "J2") (pin "2") (pinfunction "2_2") (pintype "passive"))
    )
    (net (code "87") (name "MUX_S0") (class "Default")
      (node (ref "U$1") (pin "26") (pinfunction "26/A15_26") (pintype "bidirectional"))
    )
    (net (code "88") (name "MUX_S1") (class "Default")
      (node (ref "U$1") (pin "27") (pinfunction "27/A16_27") (pintype "bidirectional"))
    )
    (net (code "89") (name "MUX_S2") (class "Default")
      (node (ref "U$1") (pin "28") (pinfunction "28/A17_28") (pintype "bidirectional"))
      (node (ref "U1") (pin "14") (pinfunction "S2_14") (pintype "input"))
    )
    (net (code "90") (name "MUX_S3") (class "Default")
      (node (ref "U$1") (pin "31") (pinfunction "31/A20_31") (pintype "bidirectional"))
      (node (ref "U1") (pin "13") (pinfunction "S3_13") (pintype "input"))
    )
    (net (code "91") (name "MUX_SCL") (class "Default")
      (node (ref "J1") (pin "6") (pinfunction "6_6") (pintype "passive"))
      (node (ref "J2") (pin "6") (pinfunction "6_6") (pintype "passive"))
      (node (ref "U$1") (pin "19/A5") (pinfunction "19/A5/T/SCL0_19/A5") (pintype "bidirectional"))
    )
    (net (code "92") (name "MUX_SDA") (class "Default")
      (node (ref "J1") (pin "5") (pinfunction "5_5") (pintype "passive"))
      (node (ref "J2") (pin "5") (pinfunction "5_5") (pintype "passive"))
      (node (ref "U$1") (pin "18/A4") (pinfunction "18/A4/T/SDA0_18/A4") (pintype "bidirectional"))
    )
    (net (code "93") (name "MUX_SIG") (class "Default")
      (node (ref "U$1") (pin "A13") (pinfunction "A13_A13") (pintype "bidirectional"))
      (node (ref "U1") (pin "1") (pinfunction "COM_1") (pintype "bidirectional"))
    )
    (net (code "94") (name "MUX_SO") (class "Default")
      (node (ref "U1") (pin "10") (pinfunction "S0_10") (pintype "input"))
    )
    (net (code "95") (name "NEO_PIXEL") (class "Default")
      (node (ref "CONN02") (pin "7") (pinfunction "7_7") (pintype "bidirectional"))
      (node (ref "U$1") (pin "2") (pinfunction "2_2") (pintype "bidirectional"))
    )
    (net (code "96") (name "Net-(CAN_LED-A)") (class "Default")
      (node (ref "CAN_LED") (pin "1") (pinfunction "A_1") (pintype "passive"))
      (node (ref "CAN_LED_R") (pin "1") (pinfunction "1_1") (pintype "passive"))
    )
    (net (code "97") (name "Net-(POWER_LED-A)") (class "Default")
      (node (ref "POWER_LED") (pin "1") (pinfunction "A_1") (pintype "passive"))
      (node (ref "POWER_LED_RES") (pin "1") (pinfunction "1_1") (pintype "passive"))
    )
    (net (code "98") (name "Net-(U1-CHAN0)") (class "Default")
      (node (ref "SW1") (pin "20") (pinfunction "20_20") (pintype "passive"))
      (node (ref "U1") (pin "9") (pinfunction "CHAN0_9") (pintype "bidirectional"))
    )
    (net (code "99") (name "Net-(U1-CHAN1)") (class "Default")
      (node (ref "SW1") (pin "19") (pinfunction "19_19") (pintype "passive"))
      (node (ref "U1") (pin "8") (pinfunction "CHAN1_8") (pintype "bidirectional"))
    )
    (net (code "100") (name "Net-(U1-CHAN2)") (class "Default")
      (node (ref "SW1") (pin "18") (pinfunction "18_18") (pintype "passive"))
      (node (ref "U1") (pin "7") (pinfunction "CHAN2_7") (pintype "bidirectional"))
    )
    (net (code "101") (name "Net-(U1-CHAN3)") (class "Default")
      (node (ref "SW1") (pin "17") (pinfunction "17_17") (pintype "passive"))
      (node (ref "U1") (pin "6") (pinfunction "CHAN3_6") (pintype "bidirectional"))
    )
    (net (code "102") (name "Net-(U1-CHAN4)") (class "Default")
      (node (ref "SW1") (pin "16") (pinfunction "16_16") (pintype "passive"))
      (node (ref "U1") (pin "5") (pinfunction "CHAN4_5") (pintype "bidirectional"))
    )
    (net (code "103") (name "Net-(U1-CHAN5)") (class "Default")
      (node (ref "SW1") (pin "15") (pinfunction "15_15") (pintype "passive"))
      (node (ref "U1") (pin "4") (pinfunction "CHAN5_4") (pintype "bidirectional"))
    )
    (net (code "104") (name "Net-(U1-CHAN6)") (class "Default")
      (node (ref "SW1") (pin "14") (pinfunction "14_14") (pintype "passive"))
      (node (ref "U1") (pin "3") (pinfunction "CHAN6_3") (pintype "bidirectional"))
    )
    (net (code "105") (name "Net-(U1-CHAN7)") (class "Default")
      (node (ref "SW1") (pin "13") (pinfunction "13_13") (pintype "passive"))
      (node (ref "U1") (pin "2") (pinfunction "CHAN7_2") (pintype "bidirectional"))
    )
    (net (code "106") (name "Net-(U1-CHAN8)") (class "Default")
      (node (ref "SW1") (pin "12") (pinfunction "12_12") (pintype "passive"))
      (node (ref "U1") (pin "23") (pinfunction "CHAN8_23") (pintype "bidirectional"))
    )
    (net (code "107") (name "Net-(U1-CHAN9)") (class "Default")
      (node (ref "SW1") (pin "11") (pinfunction "11_11") (pintype "passive"))
      (node (ref "U1") (pin "22") (pinfunction "CHAN9_22") (pintype "bidirectional"))
    )
    (net (code "108") (name "S_SCL") (class "Default")
      (node (ref "CONN02") (pin "10") (pinfunction "10_10") (pintype "bidirectional"))
      (node (ref "U$1") (pin "29") (pinfunction "29/A18/SCL1_29") (pintype "bidirectional"))
    )
    (net (code "109") (name "S_SDA") (class "Default")
      (node (ref "CONN02") (pin "9") (pinfunction "9_9") (pintype "bidirectional"))
      (node (ref "U$1") (pin "30") (pinfunction "30/A19/SDA1_30") (pintype "bidirectional"))
    )
    (net (code "110") (name "S_SEN_01") (class "Default")
      (node (ref "CONN02") (pin "8") (pinfunction "8_8") (pintype "bidirectional"))
      (node (ref "U$1") (pin "A12") (pinfunction "A12_A12") (pintype "bidirectional"))
    )
    (net (code "111") (name "VCC1") (class "Default")
      (node (ref "J3") (pin "5") (pinfunction "5_5") (pintype "passive"))
    )
    (net (code "112") (name "VCC2") (class "Default")
      (node (ref "J4") (pin "5") (pinfunction "5_5") (pintype "passive"))
    )
    (net (code "113") (name "VCC_M") (class "Default")
      (node (ref "INPUT_POWER") (pin "VCC_01") (pinfunction "VCC_01_VCC_01") (pintype "bidirectional"))
      (node (ref "MOTOR_01") (pin "VCC") (pinfunction "VCC_VCC") (pintype "bidirectional"))
      (node (ref "MOTOR_02") (pin "VCC") (pinfunction "VCC_VCC") (pintype "bidirectional"))
      (node (ref "MOTOR_03") (pin "VCC") (pinfunction "VCC_VCC") (pintype "bidirectional"))
      (node (ref "MOTOR_04") (pin "VCC") (pinfunction "VCC_VCC") (pintype "bidirectional"))
      (node (ref "MOTOR_05") (pin "VCC") (pinfunction "VCC_VCC") (pintype "bidirectional"))
      (node (ref "MOTOR_06") (pin "VCC") (pinfunction "VCC_VCC") (pintype "bidirectional"))
      (node (ref "MOTOR_07") (pin "VCC") (pinfunction "VCC_VCC") (pintype "bidirectional"))
      (node (ref "MOTOR_08") (pin "VCC") (pinfunction "VCC_VCC") (pintype "bidirectional"))
      (node (ref "M_C10") (pin "1") (pinfunction "1_1") (pintype "passive"))
      (node (ref "M_C11") (pin "1") (pinfunction "1_1") (pintype "passive"))
      (node (ref "M_C4") (pin "1") (pinfunction "1_1") (pintype "passive"))
      (node (ref "M_C5") (pin "1") (pinfunction "1_1") (pintype "passive"))
      (node (ref "M_C6") (pin "1") (pinfunction "1_1") (pintype "passive"))
      (node (ref "M_C7") (pin "1") (pinfunction "1_1") (pintype "passive"))
      (node (ref "M_C8") (pin "1") (pinfunction "1_1") (pintype "passive"))
      (node (ref "M_C9") (pin "1") (pinfunction "1_1") (pintype "passive"))
      (node (ref "OUTPUT_POWER") (pin "VCC_01") (pinfunction "VCC_01_VCC_01") (pintype "bidirectional"))
      (node (ref "POWER_LED_RES") (pin "2") (pinfunction "2_2") (pintype "passive"))
    )
    (net (code "114") (name "VCC_MCU") (class "Default")
      (node (ref "C2") (pin "2") (pinfunction "2_2") (pintype "passive"))
      (node (ref "C3") (pin "1") (pinfunction "1_1") (pintype "passive"))
      (node (ref "CONN01") (pin "11") (pinfunction "11_11") (pintype "bidirectional"))
      (node (ref "CONN02") (pin "11") (pinfunction "11_11") (pintype "bidirectional"))
      (node (ref "INPUT_POWER") (pin "VCC_02") (pinfunction "VCC_02_VCC_02") (pintype "bidirectional"))
      (node (ref "OUTPUT_POWER") (pin "VCC_02") (pinfunction "VCC_02_VCC_02") (pintype "bidirectional"))
      (node (ref "TCAN1042") (pin "3") (pinfunction "VCC_3") (pintype "power_in"))
      (node (ref "U$1") (pin "VIN") (pinfunction "VIN_VIN") (pintype "power_in"))
    )
    (net (code "115") (name "unconnected-(J3-Pad10)") (class "Default")
      (node (ref "J3") (pin "10") (pinfunction "10_10") (pintype "passive"))
    )
    (net (code "116") (name "unconnected-(J4-Pad10)") (class "Default")
      (node (ref "J4") (pin "10") (pinfunction "10_10") (pintype "passive"))
    )
    (net (code "117") (name "unconnected-(MOTOR_01-Pad1)") (class "Default")
      (node (ref "MOTOR_01") (pin "1") (pinfunction "1_1") (pintype "bidirectional"))
    )
    (net (code "118") (name "unconnected-(MOTOR_01-Pad2)") (class "Default")
      (node (ref "MOTOR_01") (pin "2") (pinfunction "2_2") (pintype "bidirectional"))
    )
    (net (code "119") (name "unconnected-(MOTOR_01-PadSTBY)") (class "Default")
      (node (ref "MOTOR_01") (pin "STBY") (pinfunction "STBY_STBY") (pintype "bidirectional"))
    )
    (net (code "120") (name "unconnected-(MOTOR_01-PadVMOT)") (class "Default")
      (node (ref "MOTOR_01") (pin "VMOT") (pinfunction "VMOT_VMOT") (pintype "bidirectional"))
    )
    (net (code "121") (name "unconnected-(MOTOR_02-Pad1)") (class "Default")
      (node (ref "MOTOR_02") (pin "1") (pinfunction "1_1") (pintype "bidirectional"))
    )
    (net (code "122") (name "unconnected-(MOTOR_02-Pad2)") (class "Default")
      (node (ref "MOTOR_02") (pin "2") (pinfunction "2_2") (pintype "bidirectional"))
    )
    (net (code "123") (name "unconnected-(MOTOR_02-PadSTBY)") (class "Default")
      (node (ref "MOTOR_02") (pin "STBY") (pinfunction "STBY_STBY") (pintype "bidirectional"))
    )
    (net (code "124") (name "unconnected-(MOTOR_02-PadVMOT)") (class "Default")
      (node (ref "MOTOR_02") (pin "VMOT") (pinfunction "VMOT_VMOT") (pintype "bidirectional"))
    )
    (net (code "125") (name "unconnected-(MOTOR_03-Pad1)") (class "Default")
      (node (ref "MOTOR_03") (pin "1") (pinfunction "1_1") (pintype "bidirectional"))
    )
    (net (code "126") (name "unconnected-(MOTOR_03-Pad2)") (class "Default")
      (node (ref "MOTOR_03") (pin "2") (pinfunction "2_2") (pintype "bidirectional"))
    )
    (net (code "127") (name "unconnected-(MOTOR_03-PadSTBY)") (class "Default")
      (node (ref "MOTOR_03") (pin "STBY") (pinfunction "STBY_STBY") (pintype "bidirectional"))
    )
    (net (code "128") (name "unconnected-(MOTOR_03-PadVMOT)") (class "Default")
      (node (ref "MOTOR_03") (pin "VMOT") (pinfunction "VMOT_VMOT") (pintype "bidirectional"))
    )
    (net (code "129") (name "unconnected-(MOTOR_04-Pad1)") (class "Default")
      (node (ref "MOTOR_04") (pin "1") (pinfunction "1_1") (pintype "bidirectional"))
    )
    (net (code "130") (name "unconnected-(MOTOR_04-Pad2)") (class "Default")
      (node (ref "MOTOR_04") (pin "2") (pinfunction "2_2") (pintype "bidirectional"))
    )
    (net (code "131") (name "unconnected-(MOTOR_04-PadSTBY)") (class "Default")
      (node (ref "MOTOR_04") (pin "STBY") (pinfunction "STBY_STBY") (pintype "bidirectional"))
    )
    (net (code "132") (name "unconnected-(MOTOR_04-PadVMOT)") (class "Default")
      (node (ref "MOTOR_04") (pin "VMOT") (pinfunction "VMOT_VMOT") (pintype "bidirectional"))
    )
    (net (code "133") (name "unconnected-(MOTOR_05-Pad1)") (class "Default")
      (node (ref "MOTOR_05") (pin "1") (pinfunction "1_1") (pintype "bidirectional"))
    )
    (net (code "134") (name "unconnected-(MOTOR_05-Pad2)") (class "Default")
      (node (ref "MOTOR_05") (pin "2") (pinfunction "2_2") (pintype "bidirectional"))
    )
    (net (code "135") (name "unconnected-(MOTOR_05-PadSTBY)") (class "Default")
      (node (ref "MOTOR_05") (pin "STBY") (pinfunction "STBY_STBY") (pintype "bidirectional"))
    )
    (net (code "136") (name "unconnected-(MOTOR_05-PadVMOT)") (class "Default")
      (node (ref "MOTOR_05") (pin "VMOT") (pinfunction "VMOT_VMOT") (pintype "bidirectional"))
    )
    (net (code "137") (name "unconnected-(MOTOR_06-Pad1)") (class "Default")
      (node (ref "MOTOR_06") (pin "1") (pinfunction "1_1") (pintype "bidirectional"))
    )
    (net (code "138") (name "unconnected-(MOTOR_06-Pad2)") (class "Default")
      (node (ref "MOTOR_06") (pin "2") (pinfunction "2_2") (pintype "bidirectional"))
    )
    (net (code "139") (name "unconnected-(MOTOR_06-PadSTBY)") (class "Default")
      (node (ref "MOTOR_06") (pin "STBY") (pinfunction "STBY_STBY") (pintype "bidirectional"))
    )
    (net (code "140") (name "unconnected-(MOTOR_06-PadVMOT)") (class "Default")
      (node (ref "MOTOR_06") (pin "VMOT") (pinfunction "VMOT_VMOT") (pintype "bidirectional"))
    )
    (net (code "141") (name "unconnected-(MOTOR_07-Pad1)") (class "Default")
      (node (ref "MOTOR_07") (pin "1") (pinfunction "1_1") (pintype "bidirectional"))
    )
    (net (code "142") (name "unconnected-(MOTOR_07-Pad2)") (class "Default")
      (node (ref "MOTOR_07") (pin "2") (pinfunction "2_2") (pintype "bidirectional"))
    )
    (net (code "143") (name "unconnected-(MOTOR_07-PadSTBY)") (class "Default")
      (node (ref "MOTOR_07") (pin "STBY") (pinfunction "STBY_STBY") (pintype "bidirectional"))
    )
    (net (code "144") (name "unconnected-(MOTOR_07-PadVMOT)") (class "Default")
      (node (ref "MOTOR_07") (pin "VMOT") (pinfunction "VMOT_VMOT") (pintype "bidirectional"))
    )
    (net (code "145") (name "unconnected-(MOTOR_08-Pad1)") (class "Default")
      (node (ref "MOTOR_08") (pin "1") (pinfunction "1_1") (pintype "bidirectional"))
    )
    (net (code "146") (name "unconnected-(MOTOR_08-Pad2)") (class "Default")
      (node (ref "MOTOR_08") (pin "2") (pinfunction "2_2") (pintype "bidirectional"))
    )
    (net (code "147") (name "unconnected-(MOTOR_08-PadSTBY)") (class "Default")
      (node (ref "MOTOR_08") (pin "STBY") (pinfunction "STBY_STBY") (pintype "bidirectional"))
    )
    (net (code "148") (name "unconnected-(MOTOR_08-PadVMOT)") (class "Default")
      (node (ref "MOTOR_08") (pin "VMOT") (pinfunction "VMOT_VMOT") (pintype "bidirectional"))
    )
    (net (code "149") (name "unconnected-(TCAN1042-NC-Pad5)") (class "Default")
      (node (ref "TCAN1042") (pin "5") (pinfunction "NC_5") (pintype "passive"))
    )
    (net (code "150") (name "unconnected-(U$1-0{slash}RX1{slash}T-Pad0)") (class "Default")
      (node (ref "U$1") (pin "0") (pinfunction "0/RX1/T_0") (pintype "bidirectional"))
    )
    (net (code "151") (name "unconnected-(U$1-1{slash}TX1{slash}T-Pad1)") (class "Default")
      (node (ref "U$1") (pin "1") (pinfunction "1/TX1/T_1") (pintype "bidirectional"))
    )
    (net (code "152") (name "unconnected-(U$1-13{slash}SCK{slash}LED-Pad13)") (class "Default")
      (node (ref "U$1") (pin "13") (pinfunction "13/SCK/LED_13") (pintype "bidirectional"))
    )
    (net (code "153") (name "unconnected-(U$1-A14{slash}DAC-PadRESET{slash}DAC)") (class "Default")
      (node (ref "U$1") (pin "RESET/DAC") (pinfunction "A14/DAC_RESET/DAC") (pintype "bidirectional"))
    )
    (net (code "154") (name "unconnected-(U$1-PadA10)") (class "Default")
      (node (ref "U$1") (pin "A10") (pinfunction "A10_A10") (pintype "bidirectional"))
    )
    (net (code "155") (name "unconnected-(U$1-PadA11)") (class "Default")
      (node (ref "U$1") (pin "A11") (pinfunction "A11_A11") (pintype "bidirectional"))
    )
    (net (code "156") (name "unconnected-(U$1-PadPGM)") (class "Default")
      (node (ref "U$1") (pin "PGM") (pinfunction "PGM_PGM") (pintype "bidirectional"))
    )
    (net (code "157") (name "unconnected-(U1-CHAN10-Pad21)") (class "Default")
      (node (ref "U1") (pin "21") (pinfunction "CHAN10_21") (pintype "bidirectional"))
    )
    (net (code "158") (name "unconnected-(U1-CHAN11-Pad20)") (class "Default")
      (node (ref "U1") (pin "20") (pinfunction "CHAN11_20") (pintype "bidirectional"))
    )
    (net (code "159") (name "unconnected-(U1-CHAN12-Pad19)") (class "Default")
      (node (ref "U1") (pin "19") (pinfunction "CHAN12_19") (pintype "bidirectional"))
    )
    (net (code "160") (name "unconnected-(U1-CHAN13-Pad18)") (class "Default")
      (node (ref "U1") (pin "18") (pinfunction "CHAN13_18") (pintype "bidirectional"))
    )
    (net (code "161") (name "unconnected-(U1-CHAN14-Pad17)") (class "Default")
      (node (ref "U1") (pin "17") (pinfunction "CHAN14_17") (pintype "bidirectional"))
    )
    (net (code "162") (name "unconnected-(U1-CHAN15-Pad16)") (class "Default")
      (node (ref "U1") (pin "16") (pinfunction "CHAN15_16") (pintype "bidirectional"))
    )
  )
)
